# 220_power.net
KiCad netlist of a schematic drawn in EAGLE
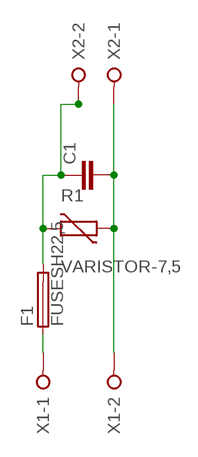
[diagram p0: schematic, sheet 1]

(export (version "E")
  (design (tool "Eeschema 10.0.6"))
  (components
    (comp (ref "C1")
      (value "C15/8")
      (footprint "eagle-import:C15B8")
      (libsource (lib "eagle-import") (part "C15/8"))
    )
    (comp (ref "F1")
      (value "FUSESH22,5")
      (footprint "eagle-import:SH22,5")
      (libsource (lib "eagle-import") (part "FUSESH22,5"))
    )
    (comp (ref "R1")
      (value "VARISTOR-7,5")
      (footprint "eagle-import:R-7,5")
      (libsource (lib "eagle-import") (part "VARISTOR-7,5"))
    )
    (comp (ref "X1")
      (value "W237-02P")
      (footprint "eagle-import:W237-132")
      (libsource (lib "eagle-import") (part "W237-02P"))
    )
    (comp (ref "X2")
      (value "W237-02P")
      (footprint "eagle-import:W237-132")
      (libsource (lib "eagle-import") (part "W237-02P"))
    )
  )
  (nets
    (net (code "1") (name "Net-(X1A-KL)") (class "Default")
      (node (ref "F1") (pin "1") (pinfunction "1_1") (pintype "passive"))
      (node (ref "X1") (pin "1") (pinfunction "KL_1") (pintype "passive"))
    )
    (net (code "2") (name "Net-(X1B-KL)") (class "Default")
      (node (ref "C1") (pin "2") (pinfunction "2_2") (pintype "passive"))
      (node (ref "R1") (pin "1") (pinfunction "1_1") (pintype "passive"))
      (node (ref "X1") (pin "2") (pinfunction "KL_2") (pintype "passive"))
      (node (ref "X2") (pin "1") (pinfunction "KL_1") (pintype "passive"))
    )
    (net (code "3") (name "Net-(X2B-KL)") (class "Default")
      (node (ref "C1") (pin "1") (pinfunction "1_1") (pintype "passive"))
      (node (ref "F1") (pin "2") (pinfunction "2_2") (pintype "passive"))
      (node (ref "R1") (pin "2") (pinfunction "2_2") (pintype "passive"))
      (node (ref "X2") (pin "2") (pinfunction "KL_2") (pintype "passive"))
    )
  )
)
